# Cursor-EC60.net
KiCad netlist of a schematic drawn in EAGLE
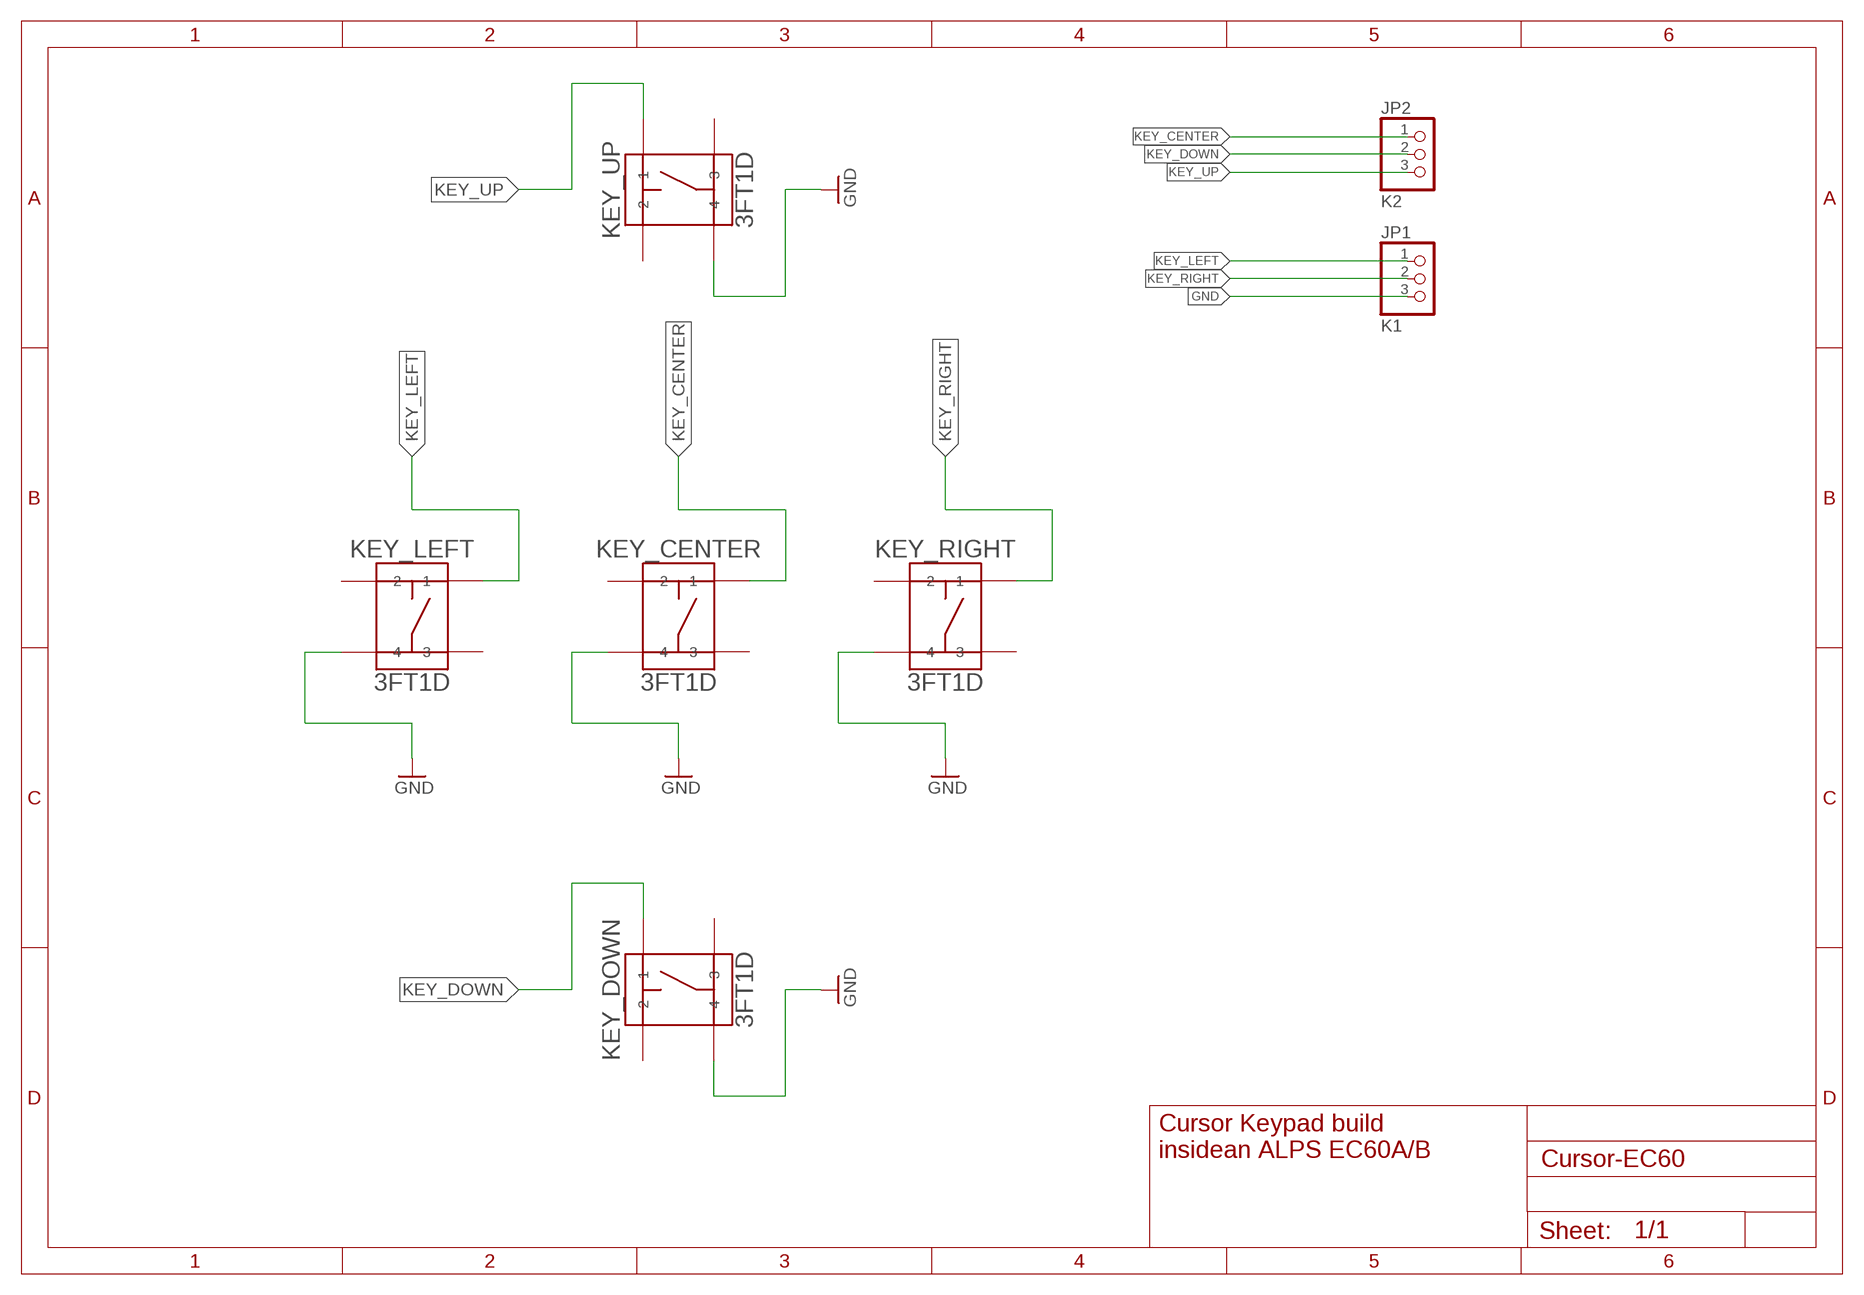
[diagram p0: schematic, sheet 1]

(export (version "E")
  (design (tool "Eeschema 10.0.6"))
  (components
    (comp (ref "JP1")
      (value "K1")
      (footprint "eagle-import:1X03")
      (libsource (lib "eagle-import") (part "PINHD-1X3"))
    )
    (comp (ref "JP2")
      (value "K2")
      (footprint "eagle-import:1X03")
      (libsource (lib "eagle-import") (part "PINHD-1X3"))
    )
    (comp (ref "KEY_CENTER")
      (value "3FT1D")
      (footprint "eagle-import:3FT")
      (libsource (lib "eagle-import") (part "3FT1D"))
    )
    (comp (ref "KEY_DOWN")
      (value "3FT1D")
      (footprint "eagle-import:3FT")
      (libsource (lib "eagle-import") (part "3FT1D"))
    )
    (comp (ref "KEY_LEFT")
      (value "3FT1D")
      (footprint "eagle-import:3FT")
      (libsource (lib "eagle-import") (part "3FT1D"))
    )
    (comp (ref "KEY_RIGHT")
      (value "3FT1D")
      (footprint "eagle-import:3FT")
      (libsource (lib "eagle-import") (part "3FT1D"))
    )
    (comp (ref "KEY_UP")
      (value "3FT1D")
      (footprint "eagle-import:3FT")
      (libsource (lib "eagle-import") (part "3FT1D"))
    )
  )
  (nets
    (net (code "1") (name "GND") (class "Default")
      (node (ref "JP1") (pin "3") (pinfunction "3_3") (pintype "passive"))
      (node (ref "KEY_CENTER") (pin "P$4") (pinfunction "4_P$4") (pintype "bidirectional"))
      (node (ref "KEY_DOWN") (pin "P$4") (pinfunction "4_P$4") (pintype "bidirectional"))
      (node (ref "KEY_LEFT") (pin "P$4") (pinfunction "4_P$4") (pintype "bidirectional"))
      (node (ref "KEY_RIGHT") (pin "P$4") (pinfunction "4_P$4") (pintype "bidirectional"))
      (node (ref "KEY_UP") (pin "P$4") (pinfunction "4_P$4") (pintype "bidirectional"))
    )
    (net (code "2") (name "KEY_CENTER") (class "Default")
      (node (ref "JP2") (pin "1") (pinfunction "1_1") (pintype "passive"))
      (node (ref "KEY_CENTER") (pin "P$1") (pinfunction "1_P$1") (pintype "bidirectional"))
    )
    (net (code "3") (name "KEY_DOWN") (class "Default")
      (node (ref "JP2") (pin "2") (pinfunction "2_2") (pintype "passive"))
      (node (ref "KEY_DOWN") (pin "P$1") (pinfunction "1_P$1") (pintype "bidirectional"))
    )
    (net (code "4") (name "KEY_LEFT") (class "Default")
      (node (ref "JP1") (pin "1") (pinfunction "1_1") (pintype "passive"))
      (node (ref "KEY_LEFT") (pin "P$1") (pinfunction "1_P$1") (pintype "bidirectional"))
    )
    (net (code "5") (name "KEY_RIGHT") (class "Default")
      (node (ref "JP1") (pin "2") (pinfunction "2_2") (pintype "passive"))
      (node (ref "KEY_RIGHT") (pin "P$1") (pinfunction "1_P$1") (pintype "bidirectional"))
    )
    (net (code "6") (name "KEY_UP") (class "Default")
      (node (ref "JP2") (pin "3") (pinfunction "3_3") (pintype "passive"))
      (node (ref "KEY_UP") (pin "P$1") (pinfunction "1_P$1") (pintype "bidirectional"))
    )
    (net (code "7") (name "unconnected-(KEY_CENTER-2-PadP$2)") (class "Default")
      (node (ref "KEY_CENTER") (pin "P$2") (pinfunction "2_P$2") (pintype "bidirectional"))
    )
    (net (code "8") (name "unconnected-(KEY_CENTER-3-PadP$3)") (class "Default")
      (node (ref "KEY_CENTER") (pin "P$3") (pinfunction "3_P$3") (pintype "bidirectional"))
    )
    (net (code "9") (name "unconnected-(KEY_DOWN-2-PadP$2)") (class "Default")
      (node (ref "KEY_DOWN") (pin "P$2") (pinfunction "2_P$2") (pintype "bidirectional"))
    )
    (net (code "10") (name "unconnected-(KEY_DOWN-3-PadP$3)") (class "Default")
      (node (ref "KEY_DOWN") (pin "P$3") (pinfunction "3_P$3") (pintype "bidirectional"))
    )
    (net (code "11") (name "unconnected-(KEY_LEFT-2-PadP$2)") (class "Default")
      (node (ref "KEY_LEFT") (pin "P$2") (pinfunction "2_P$2") (pintype "bidirectional"))
    )
    (net (code "12") (name "unconnected-(KEY_LEFT-3-PadP$3)") (class "Default")
      (node (ref "KEY_LEFT") (pin "P$3") (pinfunction "3_P$3") (pintype "bidirectional"))
    )
    (net (code "13") (name "unconnected-(KEY_RIGHT-2-PadP$2)") (class "Default")
      (node (ref "KEY_RIGHT") (pin "P$2") (pinfunction "2_P$2") (pintype "bidirectional"))
    )
    (net (code "14") (name "unconnected-(KEY_RIGHT-3-PadP$3)") (class "Default")
      (node (ref "KEY_RIGHT") (pin "P$3") (pinfunction "3_P$3") (pintype "bidirectional"))
    )
    (net (code "15") (name "unconnected-(KEY_UP-2-PadP$2)") (class "Default")
      (node (ref "KEY_UP") (pin "P$2") (pinfunction "2_P$2") (pintype "bidirectional"))
    )
    (net (code "16") (name "unconnected-(KEY_UP-3-PadP$3)") (class "Default")
      (node (ref "KEY_UP") (pin "P$3") (pinfunction "3_P$3") (pintype "bidirectional"))
    )
  )
)
